# USB_to_UART.net
KiCad netlist of a schematic drawn in Altium Designer
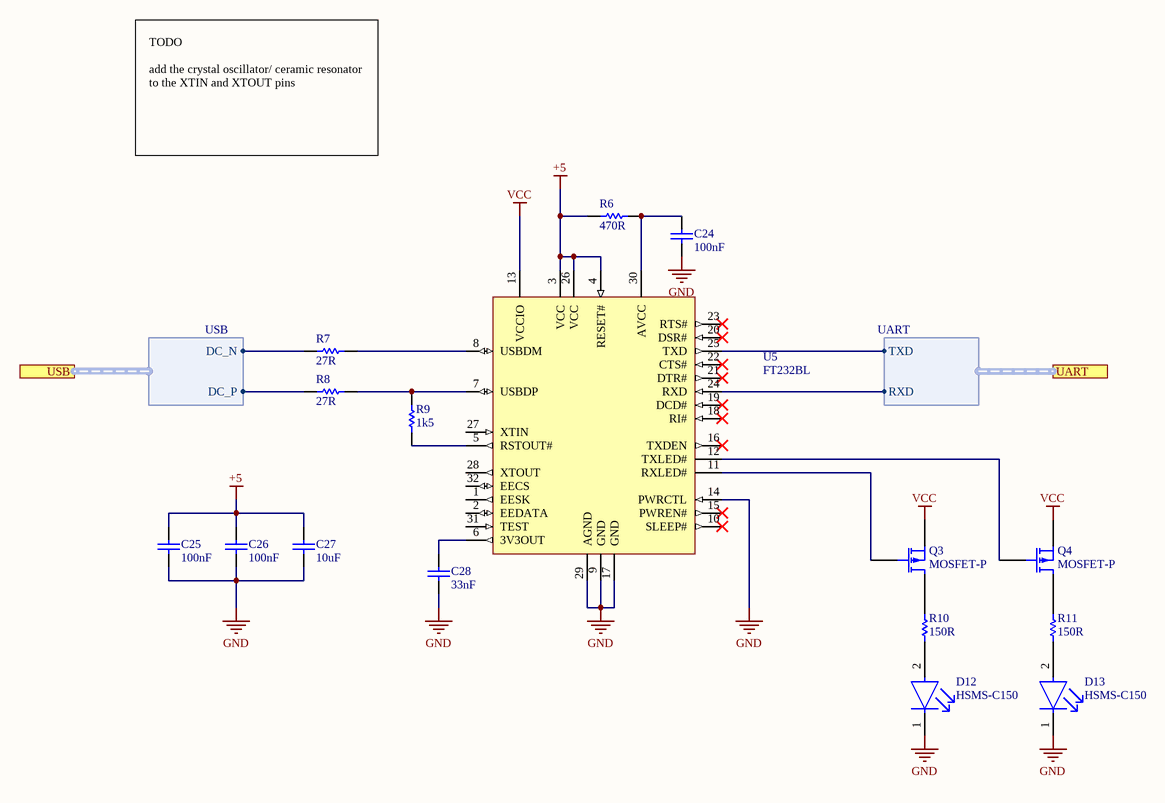
[diagram p0: USB_to_UART.SchDoc]

(export (version "E")
  (design (tool "Eeschema 10.0.6"))
  (components
    (comp (ref "C24")
      (value "100nF")
      (description "Capacitor")
      (fields (field (name "PUBLISHER") "Altium Limited"))
      (libsource (lib "Other") (part "100nF"))
    )
    (comp (ref "C25")
      (value "100nF")
      (description "Capacitor")
      (fields (field (name "PUBLISHER") "Altium Limited"))
      (libsource (lib "Other") (part "100nF"))
    )
    (comp (ref "C26")
      (value "100nF")
      (description "Capacitor")
      (fields (field (name "PUBLISHER") "Altium Limited"))
      (libsource (lib "Other") (part "100nF"))
    )
    (comp (ref "C27")
      (value "10uF")
      (description "10uF ceramic Capacitor")
      (fields (field (name "PUBLISHER") "Altium Limited"))
      (libsource (lib "Other") (part "10uF"))
    )
    (comp (ref "C28")
      (value "33nF")
      (description "33nF ceramic Capacitor")
      (fields (field (name "PUBLISHER") "Altium Limited"))
      (libsource (lib "Other") (part "33nF"))
    )
    (comp (ref "D12")
      (value "HSMS-C150")
      (footprint "FP-HSMS-C150-MFG")
      (description "LED RED DIFFUSED CHIP SMD")
      (libsource (lib "Altium Content Vault") (part "8706943c75ba83719d021d2fdc84c58"))
    )
    (comp (ref "D13")
      (value "HSMS-C150")
      (footprint "FP-HSMS-C150-MFG")
      (description "LED RED DIFFUSED CHIP SMD")
      (libsource (lib "Altium Content Vault") (part "8706943c75ba83719d021d2fdc84c58"))
    )
    (comp (ref "Q3")
      (value "MOSFET-P")
      (footprint "Tran SOT23")
      (description "P-Channel MOSFET")
      (fields (field (name "PUBLISHER") "Altium Limited"))
      (libsource (lib "Other") (part "MOSFET-P"))
    )
    (comp (ref "Q4")
      (value "MOSFET-P")
      (footprint "Tran SOT23")
      (description "P-Channel MOSFET")
      (fields (field (name "PUBLISHER") "Altium Limited"))
      (libsource (lib "Other") (part "MOSFET-P"))
    )
    (comp (ref "R6")
      (value "470R")
      (description "470 ohm Resistor")
      (fields (field (name "PUBLISHER") "Altium Limited"))
      (libsource (lib "Other") (part "470R"))
    )
    (comp (ref "R7")
      (value "27R")
      (description "Resistor")
      (fields (field (name "PUBLISHER") "Altium Limited"))
      (libsource (lib "Other") (part "27R"))
    )
    (comp (ref "R8")
      (value "27R")
      (description "Resistor")
      (fields (field (name "PUBLISHER") "Altium Limited"))
      (libsource (lib "Other") (part "27R"))
    )
    (comp (ref "R9")
      (value "1k5")
      (description "Resistor")
      (fields (field (name "PUBLISHER") "Altium Limited"))
      (libsource (lib "Other") (part "1k5"))
    )
    (comp (ref "R10")
      (value "150R")
      (footprint "RES 0603 SILK")
      (description "Resistor")
      (fields (field (name "PUBLISHER") "Altium Limited"))
      (libsource (lib "Other") (part "150R"))
    )
    (comp (ref "R11")
      (value "150R")
      (footprint "RES 0603 SILK")
      (description "Resistor")
      (fields (field (name "PUBLISHER") "Altium Limited"))
      (libsource (lib "Other") (part "150R"))
    )
    (comp (ref "U5")
      (value "FT232BL")
      (footprint "LQFP-32_L")
      (description "USB UART Asynchronous Serial Data Transfer Chip, 0 to +70 degC, 32-pin LQFP, Pb-Free")
      (fields (field (name "MANUFACTURER") "FTDI"))
      (libsource (lib "Altium Content Vault") (part "COM-UART-FT232B-SQ32A"))
    )
  )
  (nets
    (net (code "3") (name "+5") (class "Default")
      (node (ref "C25") (pin "2") (pinfunction "2_2") (pintype "passive"))
      (node (ref "C26") (pin "2") (pinfunction "2_2") (pintype "passive"))
      (node (ref "C27") (pin "2") (pinfunction "2_2") (pintype "passive"))
      (node (ref "R6") (pin "1") (pinfunction "1_1") (pintype "passive"))
      (node (ref "U5") (pin "26") (pinfunction "VCC_26") (pintype "power_in"))
      (node (ref "U5") (pin "3") (pinfunction "VCC_3") (pintype "power_in"))
      (node (ref "U5") (pin "4") (pinfunction "RESET#_4") (pintype "input"))
    )
    (net (code "4") (name "/DC_N") (class "Default")
      (node (ref "R7") (pin "1") (pinfunction "1_1") (pintype "passive"))
    )
    (net (code "5") (name "/DC_P") (class "Default")
      (node (ref "R8") (pin "1") (pinfunction "1_1") (pintype "passive"))
    )
    (net (code "6") (name "/RXD") (class "Default")
      (node (ref "U5") (pin "24") (pinfunction "RXD_24") (pintype "input"))
    )
    (net (code "7") (name "/TXD") (class "Default")
      (node (ref "U5") (pin "25") (pinfunction "TXD_25") (pintype "output"))
    )
    (net (code "10") (name "GND") (class "Default")
      (node (ref "C24") (pin "1") (pinfunction "1_1") (pintype "passive"))
      (node (ref "C25") (pin "1") (pinfunction "1_1") (pintype "passive"))
      (node (ref "C26") (pin "1") (pinfunction "1_1") (pintype "passive"))
      (node (ref "C27") (pin "1") (pinfunction "1_1") (pintype "passive"))
      (node (ref "C28") (pin "1") (pinfunction "1_1") (pintype "passive"))
      (node (ref "D12") (pin "1") (pinfunction "C_1") (pintype "passive"))
      (node (ref "D13") (pin "1") (pinfunction "C_1") (pintype "passive"))
      (node (ref "U5") (pin "14") (pinfunction "PWRCTL_14") (pintype "input"))
      (node (ref "U5") (pin "17") (pinfunction "GND_17") (pintype "power_in"))
      (node (ref "U5") (pin "29") (pinfunction "AGND_29") (pintype "power_in"))
      (node (ref "U5") (pin "9") (pinfunction "GND_9") (pintype "power_in"))
    )
    (net (code "11") (name "Net-(D12-A)") (class "Default")
      (node (ref "D12") (pin "2") (pinfunction "A_2") (pintype "passive"))
      (node (ref "R10") (pin "1") (pinfunction "1_1") (pintype "passive"))
    )
    (net (code "12") (name "Net-(D13-A)") (class "Default")
      (node (ref "D13") (pin "2") (pinfunction "A_2") (pintype "passive"))
      (node (ref "R11") (pin "1") (pinfunction "1_1") (pintype "passive"))
    )
    (net (code "13") (name "Net-(Q3-D)") (class "Default")
      (node (ref "Q3") (pin "3") (pinfunction "D_3") (pintype "passive"))
      (node (ref "R10") (pin "2") (pinfunction "2_2") (pintype "passive"))
    )
    (net (code "14") (name "Net-(Q3-G)") (class "Default")
      (node (ref "Q3") (pin "1") (pinfunction "G_1") (pintype "passive"))
      (node (ref "U5") (pin "11") (pinfunction "RXLED#_11") (pintype "open_collector"))
    )
    (net (code "15") (name "Net-(Q4-D)") (class "Default")
      (node (ref "Q4") (pin "3") (pinfunction "D_3") (pintype "passive"))
      (node (ref "R11") (pin "2") (pinfunction "2_2") (pintype "passive"))
    )
    (net (code "16") (name "Net-(Q4-G)") (class "Default")
      (node (ref "Q4") (pin "1") (pinfunction "G_1") (pintype "passive"))
      (node (ref "U5") (pin "12") (pinfunction "TXLED#_12") (pintype "open_collector"))
    )
    (net (code "17") (name "Net-(U5-3V3OUT)") (class "Default")
      (node (ref "C28") (pin "2") (pinfunction "2_2") (pintype "passive"))
      (node (ref "U5") (pin "6") (pinfunction "3V3OUT_6") (pintype "output"))
    )
    (net (code "18") (name "Net-(U5-AVCC)") (class "Default")
      (node (ref "C24") (pin "2") (pinfunction "2_2") (pintype "passive"))
      (node (ref "R6") (pin "2") (pinfunction "2_2") (pintype "passive"))
      (node (ref "U5") (pin "30") (pinfunction "AVCC_30") (pintype "power_in"))
    )
    (net (code "19") (name "Net-(U5-RSTOUT#)") (class "Default")
      (node (ref "R9") (pin "1") (pinfunction "1_1") (pintype "passive"))
      (node (ref "U5") (pin "5") (pinfunction "RSTOUT#_5") (pintype "output"))
    )
    (net (code "20") (name "Net-(U5-USBDM)") (class "Default")
      (node (ref "R7") (pin "2") (pinfunction "2_2") (pintype "passive"))
      (node (ref "U5") (pin "8") (pinfunction "USBDM_8") (pintype "bidirectional"))
    )
    (net (code "21") (name "Net-(U5-USBDP)") (class "Default")
      (node (ref "R8") (pin "2") (pinfunction "2_2") (pintype "passive"))
      (node (ref "R9") (pin "2") (pinfunction "2_2") (pintype "passive"))
      (node (ref "U5") (pin "7") (pinfunction "USBDP_7") (pintype "bidirectional"))
    )
    (net (code "22") (name "VCC") (class "Default")
      (node (ref "Q3") (pin "2") (pinfunction "S_2") (pintype "passive"))
      (node (ref "Q4") (pin "2") (pinfunction "S_2") (pintype "passive"))
      (node (ref "U5") (pin "13") (pinfunction "VCCIO_13") (pintype "power_in"))
    )
    (net (code "23") (name "unconnected-(U5-CTS#-Pad22)") (class "Default")
      (node (ref "U5") (pin "22") (pinfunction "CTS#_22") (pintype "input+no_connect"))
    )
    (net (code "24") (name "unconnected-(U5-DCD#-Pad19)") (class "Default")
      (node (ref "U5") (pin "19") (pinfunction "DCD#_19") (pintype "input+no_connect"))
    )
    (net (code "25") (name "unconnected-(U5-DSR#-Pad20)") (class "Default")
      (node (ref "U5") (pin "20") (pinfunction "DSR#_20") (pintype "input+no_connect"))
    )
    (net (code "26") (name "unconnected-(U5-DTR#-Pad21)") (class "Default")
      (node (ref "U5") (pin "21") (pinfunction "DTR#_21") (pintype "output+no_connect"))
    )
    (net (code "27") (name "unconnected-(U5-EECS-Pad32)") (class "Default")
      (node (ref "U5") (pin "32") (pinfunction "EECS_32") (pintype "bidirectional"))
    )
    (net (code "28") (name "unconnected-(U5-EEDATA-Pad2)") (class "Default")
      (node (ref "U5") (pin "2") (pinfunction "EEDATA_2") (pintype "bidirectional"))
    )
    (net (code "29") (name "unconnected-(U5-EESK-Pad1)") (class "Default")
      (node (ref "U5") (pin "1") (pinfunction "EESK_1") (pintype "output"))
    )
    (net (code "30") (name "unconnected-(U5-PWREN#-Pad15)") (class "Default")
      (node (ref "U5") (pin "15") (pinfunction "PWREN#_15") (pintype "output+no_connect"))
    )
    (net (code "31") (name "unconnected-(U5-RI#-Pad18)") (class "Default")
      (node (ref "U5") (pin "18") (pinfunction "RI#_18") (pintype "input+no_connect"))
    )
    (net (code "32") (name "unconnected-(U5-RTS#-Pad23)") (class "Default")
      (node (ref "U5") (pin "23") (pinfunction "RTS#_23") (pintype "output+no_connect"))
    )
    (net (code "33") (name "unconnected-(U5-SLEEP#-Pad10)") (class "Default")
      (node (ref "U5") (pin "10") (pinfunction "SLEEP#_10") (pintype "output+no_connect"))
    )
    (net (code "34") (name "unconnected-(U5-TEST-Pad31)") (class "Default")
      (node (ref "U5") (pin "31") (pinfunction "TEST_31") (pintype "input"))
    )
    (net (code "35") (name "unconnected-(U5-TXDEN-Pad16)") (class "Default")
      (node (ref "U5") (pin "16") (pinfunction "TXDEN_16") (pintype "output+no_connect"))
    )
    (net (code "36") (name "unconnected-(U5-XTIN-Pad27)") (class "Default")
      (node (ref "U5") (pin "27") (pinfunction "XTIN_27") (pintype "input"))
    )
    (net (code "37") (name "unconnected-(U5-XTOUT-Pad28)") (class "Default")
      (node (ref "U5") (pin "28") (pinfunction "XTOUT_28") (pintype "output"))
    )
  )
)
